# ProProject_mp3__2024-08-05.net
KiCad netlist of a schematic drawn in EasyEDA Pro
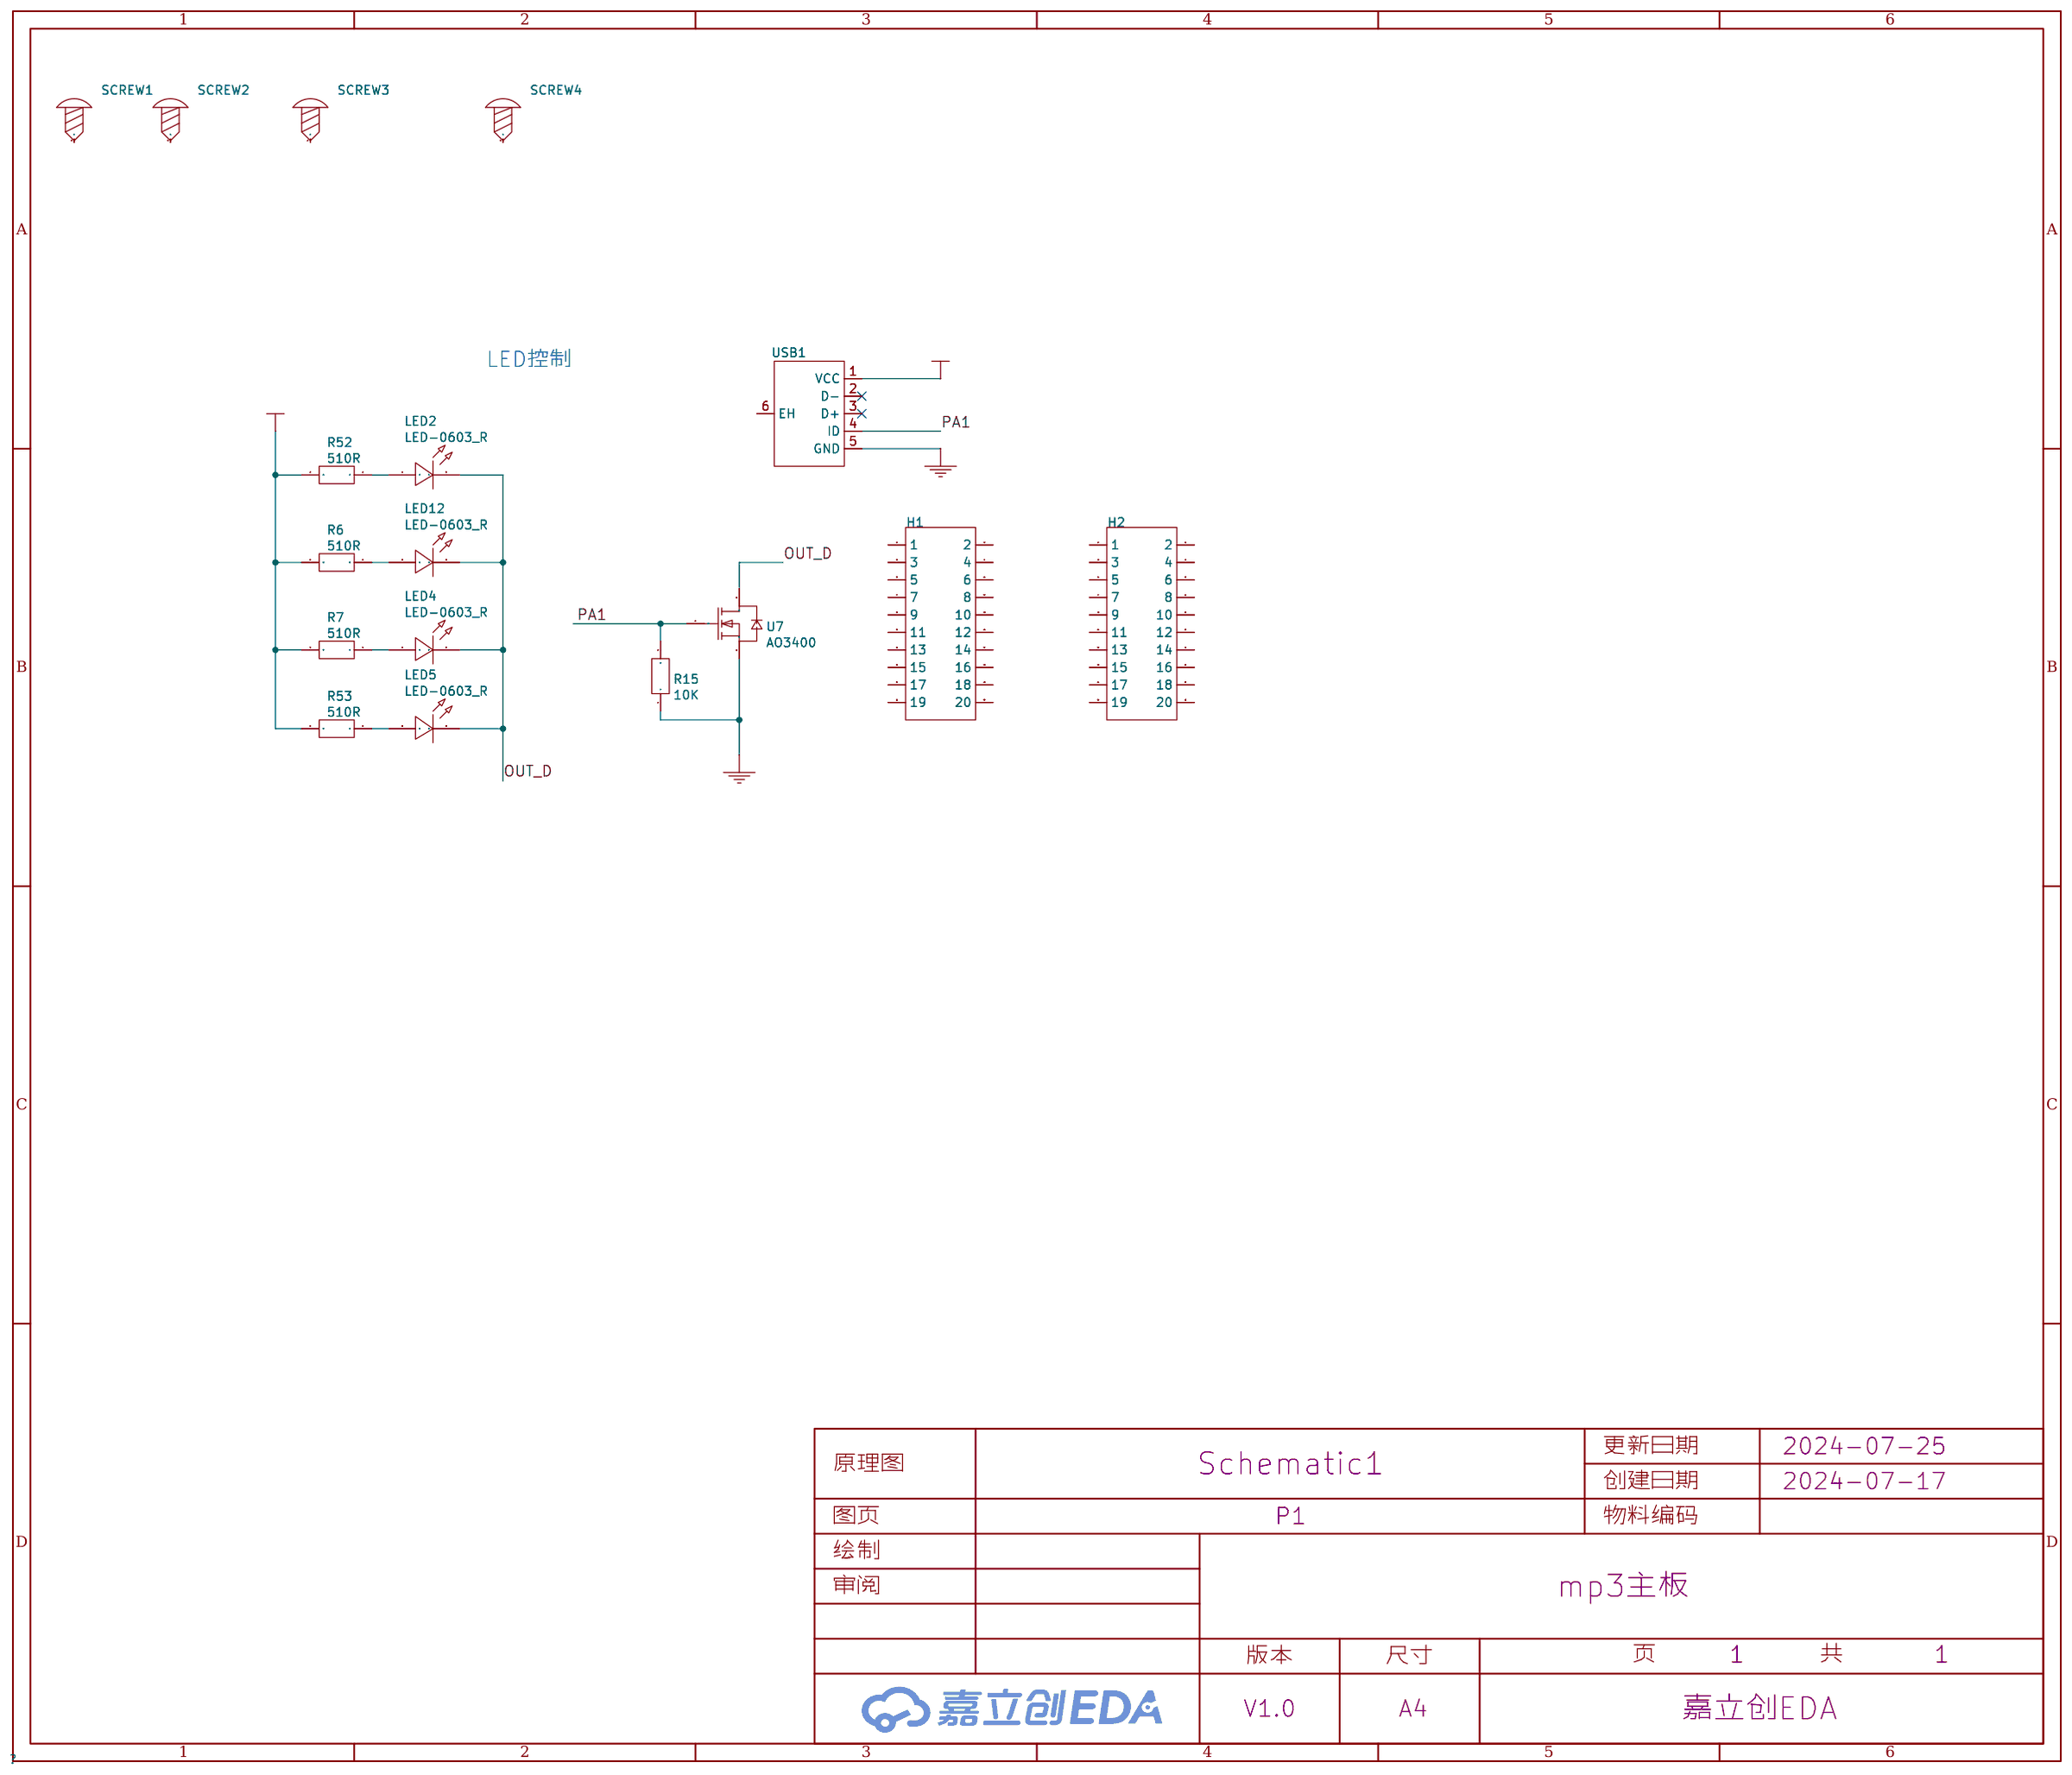
[diagram p0: schematic sheet]

(export (version "E")
  (design (tool "Eeschema 10.0.6"))
  (components
    (comp (ref "H1")
      (value "~")
      (footprint "easyedapro:HDR-TH_20P-P2.54-V-R2-C10-S2.54")
      (libsource (lib "easyedapro") (part "HDR-F-2.54_2x10"))
    )
    (comp (ref "H2")
      (value "~")
      (footprint "easyedapro:HDR-TH_20P-P2.54-V-R2-C10-S2.54")
      (libsource (lib "easyedapro") (part "HDR-F-2.54_2x10"))
    )
    (comp (ref "LED2")
      (value "LED-0603_R")
      (footprint "easyedapro:footprint_5b50")
      (fields
        (field (name "Manufacturer Part") "19-217/R6C-AL1M2VY/3T")
        (field (name "Manufacturer") "EVERLIGHT(台湾亿光)")
      )
      (libsource (lib "easyedapro") (part "LED-0603_R"))
    )
    (comp (ref "LED4")
      (value "LED-0603_R")
      (footprint "easyedapro:footprint_5b50")
      (fields
        (field (name "Manufacturer Part") "19-217/R6C-AL1M2VY/3T")
        (field (name "Manufacturer") "EVERLIGHT(台湾亿光)")
      )
      (libsource (lib "easyedapro") (part "LED-0603_R"))
    )
    (comp (ref "LED5")
      (value "LED-0603_R")
      (footprint "easyedapro:footprint_5b50")
      (fields
        (field (name "Manufacturer Part") "19-217/R6C-AL1M2VY/3T")
        (field (name "Manufacturer") "EVERLIGHT(台湾亿光)")
      )
      (libsource (lib "easyedapro") (part "LED-0603_R"))
    )
    (comp (ref "LED12")
      (value "LED-0603_R")
      (footprint "easyedapro:footprint_5b50")
      (fields
        (field (name "Manufacturer Part") "19-217/R6C-AL1M2VY/3T")
        (field (name "Manufacturer") "EVERLIGHT(台湾亿光)")
      )
      (libsource (lib "easyedapro") (part "LED-0603_R"))
    )
    (comp (ref "R6")
      (value "510R")
      (footprint "easyedapro:footprint_4dfc")
      (libsource (lib "easyedapro") (part "510R"))
    )
    (comp (ref "R7")
      (value "510R")
      (footprint "easyedapro:footprint_4dfc")
      (libsource (lib "easyedapro") (part "510R"))
    )
    (comp (ref "R15")
      (value "10K")
      (footprint "easyedapro:footprint_4dfc")
      (libsource (lib "easyedapro") (part "10K"))
    )
    (comp (ref "R52")
      (value "510R")
      (footprint "easyedapro:footprint_4dfc")
      (libsource (lib "easyedapro") (part "510R"))
    )
    (comp (ref "R53")
      (value "510R")
      (footprint "easyedapro:footprint_4dfc")
      (libsource (lib "easyedapro") (part "510R"))
    )
    (comp (ref "SCREW1")
      (value "~")
      (footprint "easyedapro:M3螺丝")
      (libsource (lib "easyedapro") (part "螺丝孔"))
    )
    (comp (ref "SCREW2")
      (value "~")
      (footprint "easyedapro:M3螺丝")
      (libsource (lib "easyedapro") (part "螺丝孔"))
    )
    (comp (ref "SCREW3")
      (value "~")
      (footprint "easyedapro:M3螺丝")
      (libsource (lib "easyedapro") (part "螺丝孔"))
    )
    (comp (ref "SCREW4")
      (value "~")
      (footprint "easyedapro:M3螺丝")
      (libsource (lib "easyedapro") (part "螺丝孔"))
    )
    (comp (ref "U7")
      (value "AO3400")
      (footprint "easyedapro:footprint_8e82")
      (fields (field (name "Manufacturer") "ElecSuper(静芯微）"))
      (libsource (lib "easyedapro") (part "AO3400"))
    )
    (comp (ref "USB1")
      (value "~")
      (footprint "easyedapro:USB_Micro")
      (libsource (lib "easyedapro") (part "USB_Micro"))
    )
  )
  (nets
    (net (code "1") (name "/OUT_D") (class "Default")
      (node (ref "LED12") (pin "2") (pinfunction "2_2") (pintype "unspecified"))
      (node (ref "LED2") (pin "2") (pinfunction "2_2") (pintype "unspecified"))
      (node (ref "LED4") (pin "2") (pinfunction "2_2") (pintype "unspecified"))
      (node (ref "LED5") (pin "2") (pinfunction "2_2") (pintype "unspecified"))
      (node (ref "U7") (pin "3") (pinfunction "D_3") (pintype "unspecified"))
    )
    (net (code "2") (name "/PA1") (class "Default")
      (node (ref "R15") (pin "2") (pinfunction "2_2") (pintype "unspecified"))
      (node (ref "U7") (pin "1") (pinfunction "G_1") (pintype "unspecified"))
      (node (ref "USB1") (pin "4") (pinfunction "ID_4") (pintype "input"))
    )
    (net (code "3") (name "3.3V") (class "Default")
      (node (ref "R52") (pin "2") (pinfunction "2_2") (pintype "unspecified"))
      (node (ref "R53") (pin "2") (pinfunction "2_2") (pintype "unspecified"))
      (node (ref "R6") (pin "2") (pinfunction "2_2") (pintype "unspecified"))
      (node (ref "R7") (pin "2") (pinfunction "2_2") (pintype "unspecified"))
      (node (ref "USB1") (pin "1") (pinfunction "VCC_1") (pintype "input"))
    )
    (net (code "4") (name "GND") (class "Default")
      (node (ref "R15") (pin "1") (pinfunction "1_1") (pintype "unspecified"))
      (node (ref "U7") (pin "2") (pinfunction "S_2") (pintype "unspecified"))
      (node (ref "USB1") (pin "5") (pinfunction "GND_5") (pintype "input"))
    )
    (net (code "5") (name "Net-(LED2-Pad1)") (class "Default")
      (node (ref "LED2") (pin "1") (pinfunction "1_1") (pintype "unspecified"))
      (node (ref "R52") (pin "1") (pinfunction "1_1") (pintype "unspecified"))
    )
    (net (code "6") (name "Net-(LED4-Pad1)") (class "Default")
      (node (ref "LED4") (pin "1") (pinfunction "1_1") (pintype "unspecified"))
      (node (ref "R7") (pin "1") (pinfunction "1_1") (pintype "unspecified"))
    )
    (net (code "7") (name "Net-(LED5-Pad1)") (class "Default")
      (node (ref "LED5") (pin "1") (pinfunction "1_1") (pintype "unspecified"))
      (node (ref "R53") (pin "1") (pinfunction "1_1") (pintype "unspecified"))
    )
    (net (code "8") (name "Net-(LED12-Pad1)") (class "Default")
      (node (ref "LED12") (pin "1") (pinfunction "1_1") (pintype "unspecified"))
      (node (ref "R6") (pin "1") (pinfunction "1_1") (pintype "unspecified"))
    )
    (net (code "9") (name "unconnected-(H1-Pad1)") (class "Default")
      (node (ref "H1") (pin "1") (pinfunction "1_1") (pintype "input"))
    )
    (net (code "10") (name "unconnected-(H1-Pad2)") (class "Default")
      (node (ref "H1") (pin "2") (pinfunction "2_2") (pintype "input"))
    )
    (net (code "11") (name "unconnected-(H1-Pad3)") (class "Default")
      (node (ref "H1") (pin "3") (pinfunction "3_3") (pintype "input"))
    )
    (net (code "12") (name "unconnected-(H1-Pad4)") (class "Default")
      (node (ref "H1") (pin "4") (pinfunction "4_4") (pintype "input"))
    )
    (net (code "13") (name "unconnected-(H1-Pad5)") (class "Default")
      (node (ref "H1") (pin "5") (pinfunction "5_5") (pintype "input"))
    )
    (net (code "14") (name "unconnected-(H1-Pad6)") (class "Default")
      (node (ref "H1") (pin "6") (pinfunction "6_6") (pintype "input"))
    )
    (net (code "15") (name "unconnected-(H1-Pad7)") (class "Default")
      (node (ref "H1") (pin "7") (pinfunction "7_7") (pintype "input"))
    )
    (net (code "16") (name "unconnected-(H1-Pad8)") (class "Default")
      (node (ref "H1") (pin "8") (pinfunction "8_8") (pintype "input"))
    )
    (net (code "17") (name "unconnected-(H1-Pad9)") (class "Default")
      (node (ref "H1") (pin "9") (pinfunction "9_9") (pintype "input"))
    )
    (net (code "18") (name "unconnected-(H1-Pad10)") (class "Default")
      (node (ref "H1") (pin "10") (pinfunction "10_10") (pintype "input"))
    )
    (net (code "19") (name "unconnected-(H1-Pad11)") (class "Default")
      (node (ref "H1") (pin "11") (pinfunction "11_11") (pintype "input"))
    )
    (net (code "20") (name "unconnected-(H1-Pad12)") (class "Default")
      (node (ref "H1") (pin "12") (pinfunction "12_12") (pintype "input"))
    )
    (net (code "21") (name "unconnected-(H1-Pad13)") (class "Default")
      (node (ref "H1") (pin "13") (pinfunction "13_13") (pintype "input"))
    )
    (net (code "22") (name "unconnected-(H1-Pad14)") (class "Default")
      (node (ref "H1") (pin "14") (pinfunction "14_14") (pintype "input"))
    )
    (net (code "23") (name "unconnected-(H1-Pad15)") (class "Default")
      (node (ref "H1") (pin "15") (pinfunction "15_15") (pintype "input"))
    )
    (net (code "24") (name "unconnected-(H1-Pad16)") (class "Default")
      (node (ref "H1") (pin "16") (pinfunction "16_16") (pintype "input"))
    )
    (net (code "25") (name "unconnected-(H1-Pad17)") (class "Default")
      (node (ref "H1") (pin "17") (pinfunction "17_17") (pintype "input"))
    )
    (net (code "26") (name "unconnected-(H1-Pad18)") (class "Default")
      (node (ref "H1") (pin "18") (pinfunction "18_18") (pintype "input"))
    )
    (net (code "27") (name "unconnected-(H1-Pad19)") (class "Default")
      (node (ref "H1") (pin "19") (pinfunction "19_19") (pintype "input"))
    )
    (net (code "28") (name "unconnected-(H1-Pad20)") (class "Default")
      (node (ref "H1") (pin "20") (pinfunction "20_20") (pintype "input"))
    )
    (net (code "29") (name "unconnected-(H2-Pad1)") (class "Default")
      (node (ref "H2") (pin "1") (pinfunction "1_1") (pintype "input"))
    )
    (net (code "30") (name "unconnected-(H2-Pad2)") (class "Default")
      (node (ref "H2") (pin "2") (pinfunction "2_2") (pintype "input"))
    )
    (net (code "31") (name "unconnected-(H2-Pad3)") (class "Default")
      (node (ref "H2") (pin "3") (pinfunction "3_3") (pintype "input"))
    )
    (net (code "32") (name "unconnected-(H2-Pad4)") (class "Default")
      (node (ref "H2") (pin "4") (pinfunction "4_4") (pintype "input"))
    )
    (net (code "33") (name "unconnected-(H2-Pad5)") (class "Default")
      (node (ref "H2") (pin "5") (pinfunction "5_5") (pintype "input"))
    )
    (net (code "34") (name "unconnected-(H2-Pad6)") (class "Default")
      (node (ref "H2") (pin "6") (pinfunction "6_6") (pintype "input"))
    )
    (net (code "35") (name "unconnected-(H2-Pad7)") (class "Default")
      (node (ref "H2") (pin "7") (pinfunction "7_7") (pintype "input"))
    )
    (net (code "36") (name "unconnected-(H2-Pad8)") (class "Default")
      (node (ref "H2") (pin "8") (pinfunction "8_8") (pintype "input"))
    )
    (net (code "37") (name "unconnected-(H2-Pad9)") (class "Default")
      (node (ref "H2") (pin "9") (pinfunction "9_9") (pintype "input"))
    )
    (net (code "38") (name "unconnected-(H2-Pad10)") (class "Default")
      (node (ref "H2") (pin "10") (pinfunction "10_10") (pintype "input"))
    )
    (net (code "39") (name "unconnected-(H2-Pad11)") (class "Default")
      (node (ref "H2") (pin "11") (pinfunction "11_11") (pintype "input"))
    )
    (net (code "40") (name "unconnected-(H2-Pad12)") (class "Default")
      (node (ref "H2") (pin "12") (pinfunction "12_12") (pintype "input"))
    )
    (net (code "41") (name "unconnected-(H2-Pad13)") (class "Default")
      (node (ref "H2") (pin "13") (pinfunction "13_13") (pintype "input"))
    )
    (net (code "42") (name "unconnected-(H2-Pad14)") (class "Default")
      (node (ref "H2") (pin "14") (pinfunction "14_14") (pintype "input"))
    )
    (net (code "43") (name "unconnected-(H2-Pad15)") (class "Default")
      (node (ref "H2") (pin "15") (pinfunction "15_15") (pintype "input"))
    )
    (net (code "44") (name "unconnected-(H2-Pad16)") (class "Default")
      (node (ref "H2") (pin "16") (pinfunction "16_16") (pintype "input"))
    )
    (net (code "45") (name "unconnected-(H2-Pad17)") (class "Default")
      (node (ref "H2") (pin "17") (pinfunction "17_17") (pintype "input"))
    )
    (net (code "46") (name "unconnected-(H2-Pad18)") (class "Default")
      (node (ref "H2") (pin "18") (pinfunction "18_18") (pintype "input"))
    )
    (net (code "47") (name "unconnected-(H2-Pad19)") (class "Default")
      (node (ref "H2") (pin "19") (pinfunction "19_19") (pintype "input"))
    )
    (net (code "48") (name "unconnected-(H2-Pad20)") (class "Default")
      (node (ref "H2") (pin "20") (pinfunction "20_20") (pintype "input"))
    )
    (net (code "49") (name "unconnected-(SCREW1-Pad1)") (class "Default")
      (node (ref "SCREW1") (pin "1") (pinfunction "1_1") (pintype "input"))
    )
    (net (code "50") (name "unconnected-(SCREW2-Pad1)") (class "Default")
      (node (ref "SCREW2") (pin "1") (pinfunction "1_1") (pintype "input"))
    )
    (net (code "51") (name "unconnected-(SCREW3-Pad1)") (class "Default")
      (node (ref "SCREW3") (pin "1") (pinfunction "1_1") (pintype "input"))
    )
    (net (code "52") (name "unconnected-(SCREW4-Pad1)") (class "Default")
      (node (ref "SCREW4") (pin "1") (pinfunction "1_1") (pintype "input"))
    )
    (net (code "53") (name "unconnected-(USB1-D+-Pad3)") (class "Default")
      (node (ref "USB1") (pin "3") (pinfunction "D+_3") (pintype "input+no_connect"))
    )
    (net (code "54") (name "unconnected-(USB1-D--Pad2)") (class "Default")
      (node (ref "USB1") (pin "2") (pinfunction "D-_2") (pintype "input+no_connect"))
    )
    (net (code "55") (name "unconnected-(USB1-EH-Pad6)") (class "Default")
      (node (ref "USB1") (pin "6") (pinfunction "EH_6") (pintype "input"))
    )
  )
)
